# HT6872_D.net
KiCad netlist of a schematic drawn in EasyEDA Pro
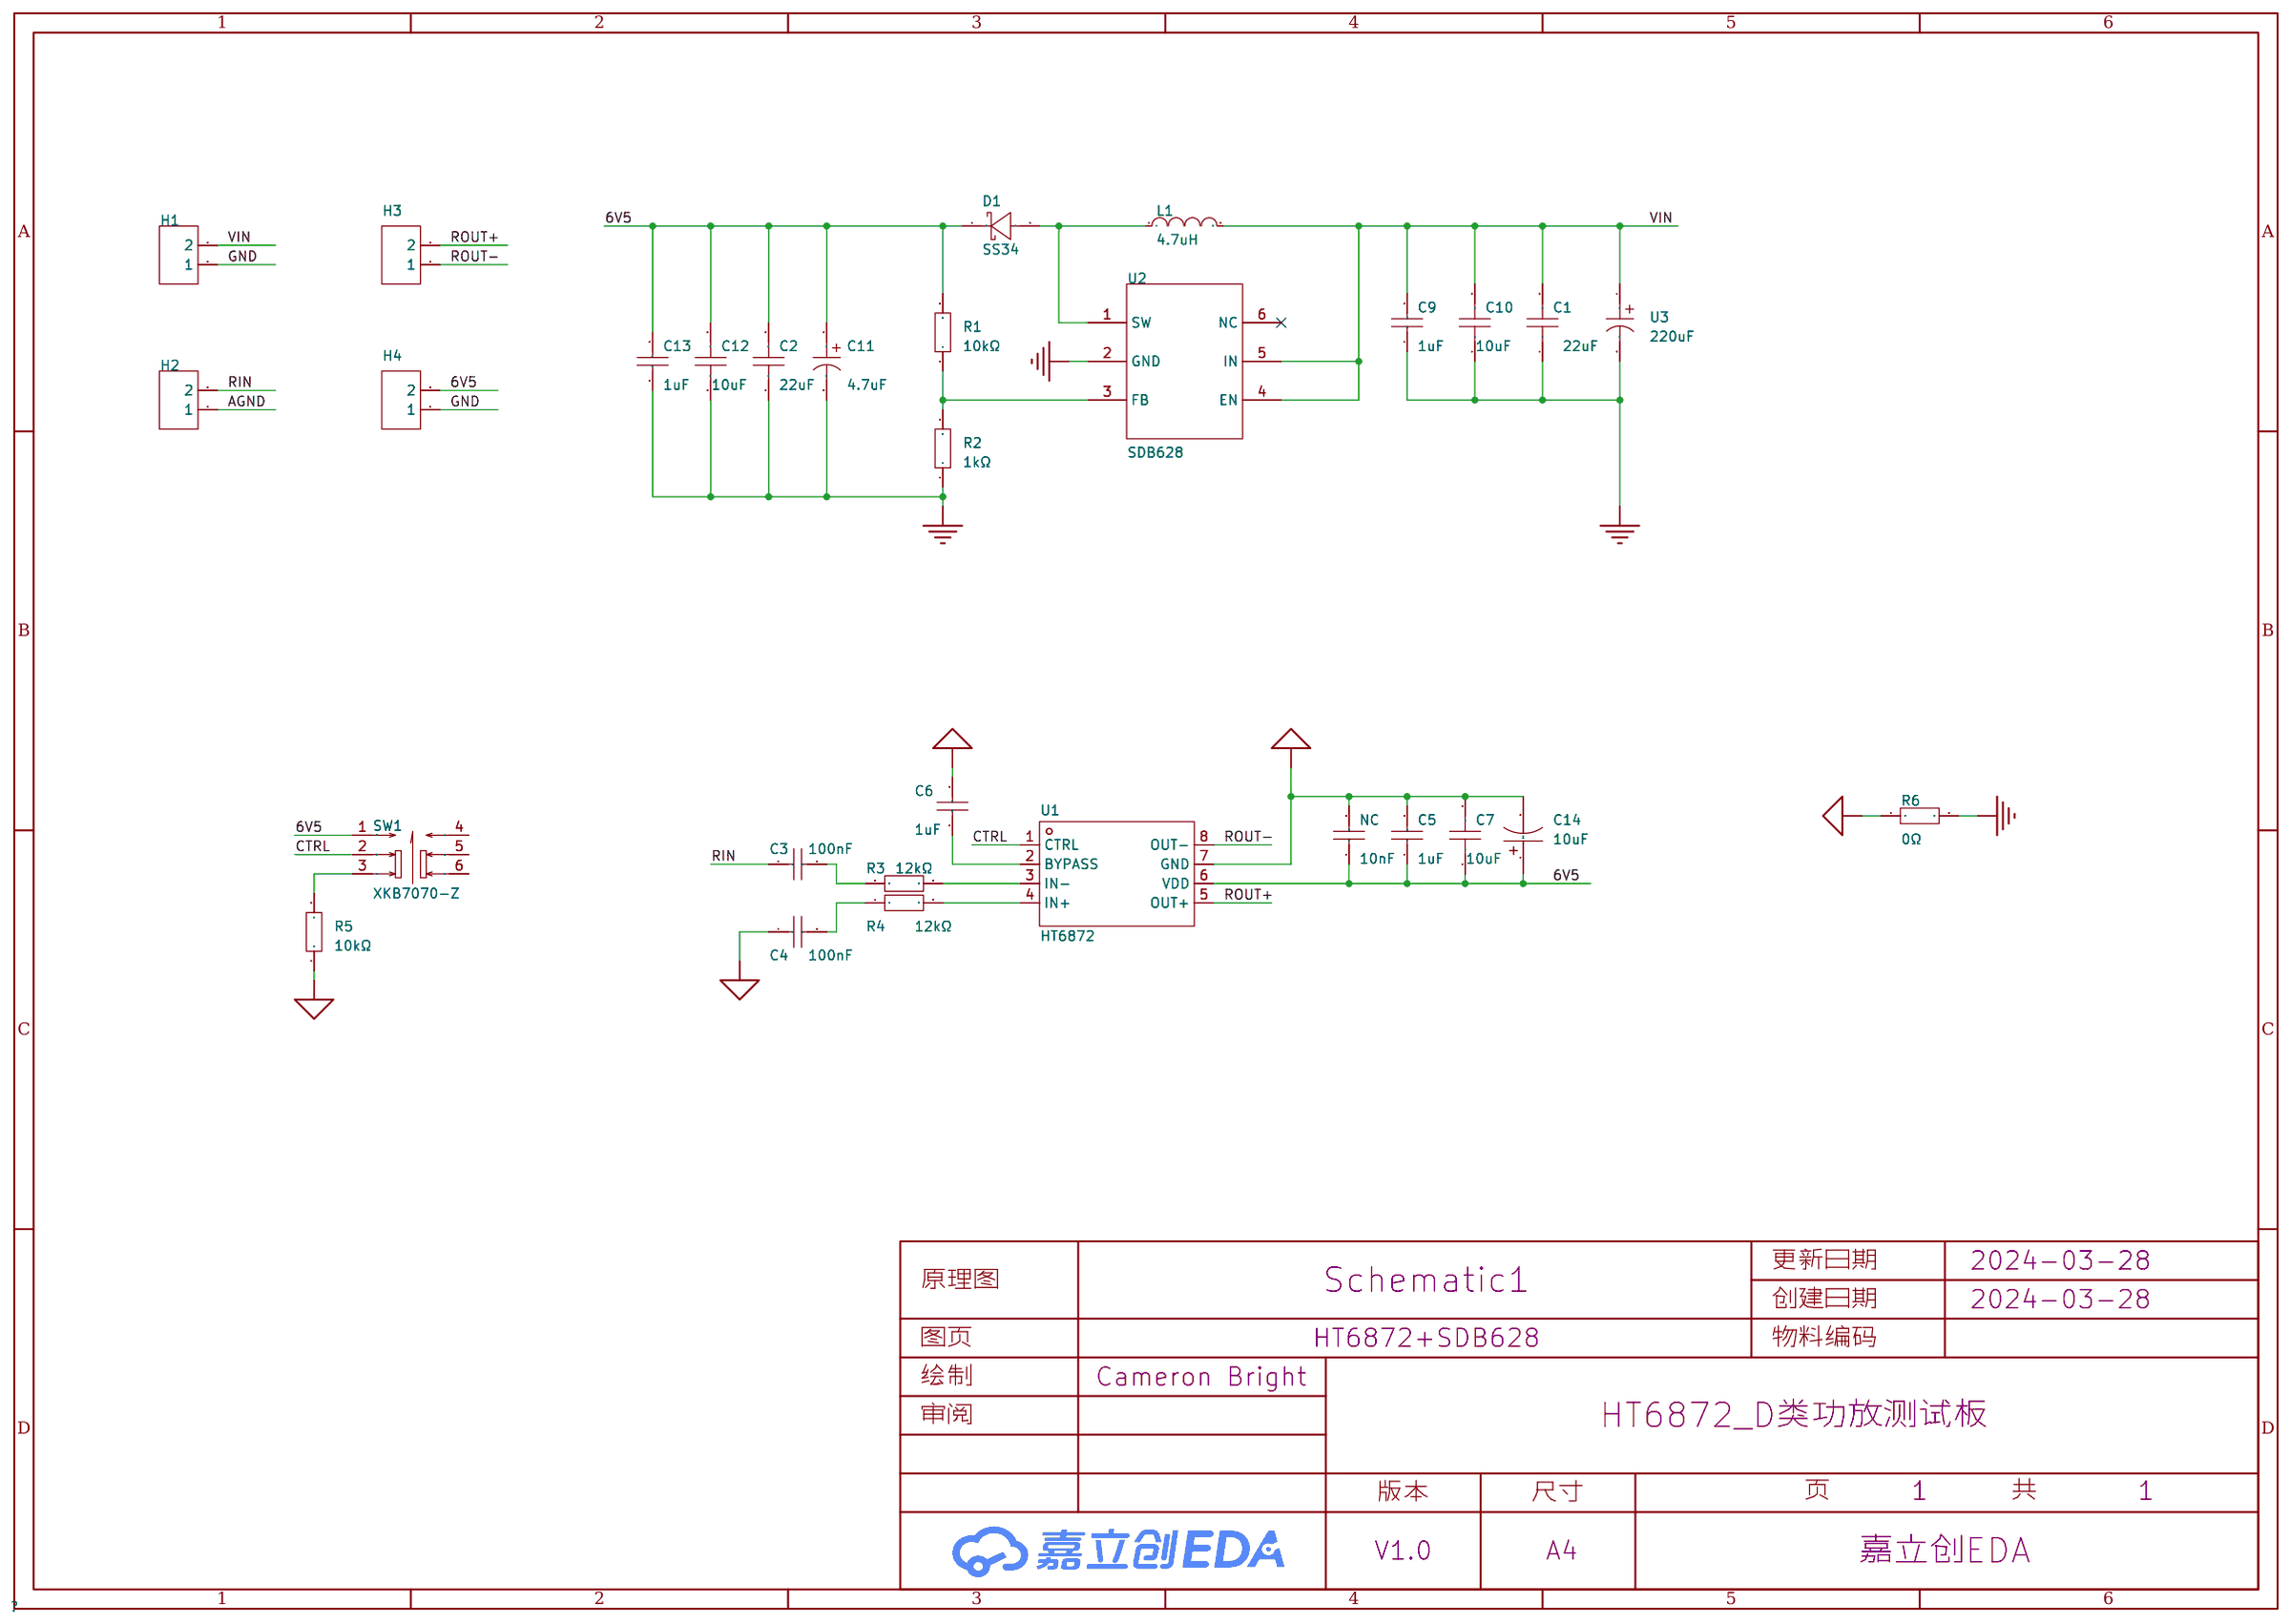
[diagram p0: schematic sheet]

(export (version "E")
  (design (tool "Eeschema 10.0.6"))
  (components
    (comp (ref "C1")
      (value "22uF")
      (footprint "easyedapro:C0603")
      (description "容值:22uF;精度:±20%;额定电压:6.3V;材质(温度系数):X5R;")
      (fields
        (field (name "Manufacturer Part") "CL10A226MQ8NRNC")
        (field (name "Manufacturer") "SAMSUNG(三星)")
      )
      (libsource (lib "easyedapro") (part "CL10A226MQ8NRNC"))
    )
    (comp (ref "C2")
      (value "22uF")
      (footprint "easyedapro:C0603")
      (description "容值:22uF;精度:±20%;额定电压:6.3V;材质(温度系数):X5R;")
      (fields
        (field (name "Manufacturer Part") "CL10A226MQ8NRNC")
        (field (name "Manufacturer") "SAMSUNG(三星)")
      )
      (libsource (lib "easyedapro") (part "CL10A226MQ8NRNC"))
    )
    (comp (ref "C3")
      (value "100nF")
      (footprint "easyedapro:C0603")
      (description "容值:100nF;精度:±10%;额定电压:50V;材质(温度系数):X7R;")
      (fields (field (name "Manufacturer Part") "0603B104K500NT") (field (name "Manufacturer") "FH(风华)"))
      (libsource (lib "easyedapro") (part "0603B104K500NT"))
    )
    (comp (ref "C4")
      (value "100nF")
      (footprint "easyedapro:C0603")
      (description "容值:100nF;精度:±10%;额定电压:50V;材质(温度系数):X7R;")
      (fields (field (name "Manufacturer Part") "0603B104K500NT") (field (name "Manufacturer") "FH(风华)"))
      (libsource (lib "easyedapro") (part "0603B104K500NT"))
    )
    (comp (ref "C5")
      (value "1uF")
      (footprint "easyedapro:C0603")
      (description "容值:1uF;精度:±10%;额定电压:50V;材质(温度系数):X5R;")
      (fields
        (field (name "Manufacturer Part") "CL10A105KB8NNNC")
        (field (name "Manufacturer") "SAMSUNG(三星)")
      )
      (libsource (lib "easyedapro") (part "CL10A105KB8NNNC"))
    )
    (comp (ref "C6")
      (value "1uF")
      (footprint "easyedapro:C0603")
      (description "容值:1uF;精度:±10%;额定电压:50V;材质(温度系数):X5R;")
      (fields
        (field (name "Manufacturer Part") "CL10A105KB8NNNC")
        (field (name "Manufacturer") "SAMSUNG(三星)")
      )
      (libsource (lib "easyedapro") (part "CL10A105KB8NNNC"))
    )
    (comp (ref "C7")
      (value "10uF")
      (footprint "easyedapro:C0603")
      (description "容值:10uF;精度:±10%;额定电压:10V;材质(温度系数):X5R;")
      (fields
        (field (name "Manufacturer Part") "CL10A106KP8NNNC")
        (field (name "Manufacturer") "SAMSUNG(三星)")
      )
      (libsource (lib "easyedapro") (part "CL10A106KP8NNNC"))
    )
    (comp (ref "C9")
      (value "1uF")
      (footprint "easyedapro:C0603")
      (description "容值:1uF;精度:±10%;额定电压:50V;材质(温度系数):X5R;")
      (fields
        (field (name "Manufacturer Part") "CL10A105KB8NNNC")
        (field (name "Manufacturer") "SAMSUNG(三星)")
      )
      (libsource (lib "easyedapro") (part "CL10A105KB8NNNC"))
    )
    (comp (ref "C10")
      (value "10uF")
      (footprint "easyedapro:C0603")
      (description "容值:10uF;精度:±10%;额定电压:10V;材质(温度系数):X5R;")
      (fields
        (field (name "Manufacturer Part") "CL10A106KP8NNNC")
        (field (name "Manufacturer") "SAMSUNG(三星)")
      )
      (libsource (lib "easyedapro") (part "CL10A106KP8NNNC"))
    )
    (comp (ref "C11")
      (value "4.7uF")
      (footprint "easyedapro:CAP-TH_BD5.0-P2.00-D0.5-FD")
      (description "容值:4.7uF;精度:±20%;额定电压:50V;纹波电流:-;等效串联电阻:-;")
      (fields (field (name "Manufacturer Part") "KM1H4R7M0407") (field (name "Manufacturer") "ROQANG(容强)"))
      (libsource (lib "easyedapro") (part "KM1H4R7M0407"))
    )
    (comp (ref "C12")
      (value "10uF")
      (footprint "easyedapro:C0603")
      (description "容值:10uF;精度:±10%;额定电压:10V;材质(温度系数):X5R;")
      (fields
        (field (name "Manufacturer Part") "CL10A106KP8NNNC")
        (field (name "Manufacturer") "SAMSUNG(三星)")
      )
      (libsource (lib "easyedapro") (part "CL10A106KP8NNNC"))
    )
    (comp (ref "C13")
      (value "1uF")
      (footprint "easyedapro:C0603")
      (description "容值:1uF;精度:±10%;额定电压:50V;材质(温度系数):X5R;")
      (fields
        (field (name "Manufacturer Part") "CL10A105KB8NNNC")
        (field (name "Manufacturer") "SAMSUNG(三星)")
      )
      (libsource (lib "easyedapro") (part "CL10A105KB8NNNC"))
    )
    (comp (ref "C14")
      (value "10uF")
      (footprint "easyedapro:CAP-TH_BD5.0-P2.00-D0.8-FD")
      (description "容值:10uF;精度:±20%;额定电压:50V;纹波电流:50mA@120Hz;等效串联电阻:-;")
      (fields
        (field (name "Manufacturer Part") "01EC1809SHC10UF50V")
        (field (name "Manufacturer") "KNSCHA(科尼盛)")
      )
      (libsource (lib "easyedapro") (part "01EC1809SHC10UF50V"))
    )
    (comp (ref "D1")
      (value "SS34")
      (footprint "easyedapro:SMA_L4.3-W2.5-LS5.0-RD")
      (description "二极管配置:独立式;正向压降(Vf):550mV@3A;直流反向耐压(Vr):40V;平均整流电流(Io):3A;")
      (fields (field (name "Manufacturer") "TWGMC(台湾迪嘉)"))
      (libsource (lib "easyedapro") (part "SS34_C727060"))
    )
    (comp (ref "H1")
      (value "~")
      (footprint "easyedapro:HDR-TH_2P-P2.54-V-F")
      (libsource (lib "easyedapro") (part "Header-Female-2.54_1x2"))
    )
    (comp (ref "H2")
      (value "~")
      (footprint "easyedapro:HDR-TH_2P-P2.54-V-F")
      (libsource (lib "easyedapro") (part "Header-Female-2.54_1x2"))
    )
    (comp (ref "H3")
      (value "~")
      (footprint "easyedapro:HDR-TH_2P-P2.54-V-F")
      (libsource (lib "easyedapro") (part "Header-Female-2.54_1x2"))
    )
    (comp (ref "H4")
      (value "~")
      (footprint "easyedapro:HDR-TH_2P-P2.54-V-F")
      (libsource (lib "easyedapro") (part "Header-Female-2.54_1x2"))
    )
    (comp (ref "L1")
      (value "4.7uH")
      (footprint "easyedapro:IND-SMD_L4.4-W4.2")
      (description "电感值:4.7uH;精度:±20%;额定电流:2.8A;饱和电流(Isat):3A;类型:一体成型电感;")
      (fields (field (name "Manufacturer Part") "FXL0420-4R7-M") (field (name "Manufacturer") "cjiang(长江微电)"))
      (libsource (lib "easyedapro") (part "FXL0420-4R7-M"))
    )
    (comp (ref "NC")
      (value "10nF")
      (footprint "easyedapro:C0603")
      (description "容值:10nF;精度:±10%;额定电压:50V;材质(温度系数):X7R;")
      (fields
        (field (name "Manufacturer Part") "CC0603KRX7R9BB103")
        (field (name "Manufacturer") "YAGEO(国巨)")
      )
      (libsource (lib "easyedapro") (part "CC0603KRX7R9BB103"))
    )
    (comp (ref "R1")
      (value "10kΩ")
      (footprint "easyedapro:R0603")
      (description "电阻类型:厚膜电阻;阻值:10kΩ;精度:±1%;功率:100mW;最大工作电压:75V;温度系数:±100ppm/°C;")
      (fields
        (field (name "Manufacturer Part") "0603WAF1002T5E")
        (field (name "Manufacturer") "UNI-ROYAL(厚声)")
      )
      (libsource (lib "easyedapro") (part "0603WAF1002T5E"))
    )
    (comp (ref "R2")
      (value "1kΩ")
      (footprint "easyedapro:R0603")
      (description "电阻类型:厚膜电阻;阻值:1kΩ;精度:±1%;功率:100mW;最大工作电压:75V;温度系数:±100ppm/°C;")
      (fields (field (name "Manufacturer Part") "RC0603FR-071KL") (field (name "Manufacturer") "YAGEO(国巨)"))
      (libsource (lib "easyedapro") (part "RC0603FR-071KL"))
    )
    (comp (ref "R3")
      (value "12kΩ")
      (footprint "easyedapro:R0603")
      (description "电阻类型:厚膜电阻;阻值:12kΩ;精度:±1%;功率:100mW;最大工作电压:75V;温度系数:±100ppm/°C;")
      (fields
        (field (name "Manufacturer Part") "0603WAF1202T5E")
        (field (name "Manufacturer") "UNI-ROYAL(厚声)")
      )
      (libsource (lib "easyedapro") (part "0603WAF1202T5E"))
    )
    (comp (ref "R4")
      (value "12kΩ")
      (footprint "easyedapro:R0603")
      (description "电阻类型:厚膜电阻;阻值:12kΩ;精度:±1%;功率:100mW;最大工作电压:75V;温度系数:±100ppm/°C;")
      (fields
        (field (name "Manufacturer Part") "0603WAF1202T5E")
        (field (name "Manufacturer") "UNI-ROYAL(厚声)")
      )
      (libsource (lib "easyedapro") (part "0603WAF1202T5E"))
    )
    (comp (ref "R5")
      (value "10kΩ")
      (footprint "easyedapro:R0603")
      (description "电阻类型:厚膜电阻;阻值:10kΩ;精度:±1%;功率:100mW;最大工作电压:75V;温度系数:±100ppm/°C;")
      (fields
        (field (name "Manufacturer Part") "0603WAF1002T5E")
        (field (name "Manufacturer") "UNI-ROYAL(厚声)")
      )
      (libsource (lib "easyedapro") (part "0603WAF1002T5E"))
    )
    (comp (ref "R6")
      (value "0Ω")
      (footprint "easyedapro:R0603")
      (description "电阻类型:厚膜电阻;阻值:0Ω;精度:±1%;功率:100mW;最大工作电压:75V;")
      (fields
        (field (name "Manufacturer Part") "0603WAF0000T5E")
        (field (name "Manufacturer") "UNI-ROYAL(厚声)")
      )
      (libsource (lib "easyedapro") (part "0603WAF0000T5E"))
    )
    (comp (ref "SW1")
      (value "XKB7070-Z")
      (footprint "easyedapro:SW-TH_6P-L7.0-W7.0-P2.00")
      (description "自锁/无锁:自锁;安装方式:直插;触点电流:100mA;额定电压 (AC):250V;额定电压 (DC):30V;带灯:不带;作用力:160gf;机械寿命:10万次;")
      (fields (field (name "Manufacturer") "XKB Connectivity(中国星坤)"))
      (libsource (lib "easyedapro") (part "XKB7070-Z"))
    )
    (comp (ref "U1")
      (value "HT6872")
      (footprint "easyedapro:SOP-8_L4.9-W3.9-P1.27-LS6.0-BL")
      (description "功放类型:D类功放;扬声器通道数:单声道;输出功率:3.85Wx1@4Ω;")
      (fields (field (name "Manufacturer") "嘉兴禾润"))
      (libsource (lib "easyedapro") (part "HT6872"))
    )
    (comp (ref "U2")
      (value "SDB628")
      (footprint "easyedapro:SOT-23-6_L2.9-W1.6-P0.95-LS2.8-BR")
      (description "功能类型:升压型;输入电压:2V~24V;输出电压:28V;输出电流(最大值):2A;")
      (fields (field (name "Manufacturer") "SHOUDING(首鼎半导体)"))
      (libsource (lib "easyedapro") (part "SDB628"))
    )
    (comp (ref "U3")
      (value "220uF")
      (footprint "easyedapro:CAP-TH_BD8.0-P3.50-D0.5-FD")
      (description "容值:220uF;精度:±20%;额定电压:35V;纹波电流:280mA@120kHz;等效串联电阻:-;")
      (fields (field (name "Manufacturer Part") "01EC1230") (field (name "Manufacturer") "KNSCHA(科尼盛)"))
      (libsource (lib "easyedapro") (part "01EC1230"))
    )
  )
  (nets
    (net (code "1") (name "/6V5") (class "Default")
      (node (ref "C11") (pin "1") (pinfunction "1_1") (pintype "input"))
      (node (ref "C12") (pin "2") (pinfunction "2_2") (pintype "unspecified"))
      (node (ref "C13") (pin "2") (pinfunction "2_2") (pintype "input"))
      (node (ref "C14") (pin "1") (pinfunction "1_1") (pintype "unspecified"))
      (node (ref "C2") (pin "2") (pinfunction "2_2") (pintype "unspecified"))
      (node (ref "C5") (pin "1") (pinfunction "1_1") (pintype "input"))
      (node (ref "C7") (pin "1") (pinfunction "1_1") (pintype "unspecified"))
      (node (ref "D1") (pin "1") (pinfunction "C_1") (pintype "unspecified"))
      (node (ref "H4") (pin "2") (pinfunction "2_2") (pintype "input"))
      (node (ref "NC") (pin "1") (pinfunction "1_1") (pintype "input"))
      (node (ref "R1") (pin "2") (pinfunction "2_2") (pintype "input"))
      (node (ref "SW1") (pin "1") (pinfunction "1_1") (pintype "unspecified"))
      (node (ref "U1") (pin "6") (pinfunction "VDD_6") (pintype "unspecified"))
    )
    (net (code "2") (name "/CTRL") (class "Default")
      (node (ref "SW1") (pin "2") (pinfunction "2_2") (pintype "unspecified"))
      (node (ref "U1") (pin "1") (pinfunction "CTRL_1") (pintype "unspecified"))
    )
    (net (code "3") (name "/RIN") (class "Default")
      (node (ref "C3") (pin "1") (pinfunction "1_1") (pintype "input"))
      (node (ref "H2") (pin "2") (pinfunction "2_2") (pintype "input"))
    )
    (net (code "4") (name "/ROUT+") (class "Default")
      (node (ref "H3") (pin "2") (pinfunction "2_2") (pintype "input"))
      (node (ref "U1") (pin "5") (pinfunction "OUT+_5") (pintype "unspecified"))
    )
    (net (code "5") (name "/ROUT-") (class "Default")
      (node (ref "H3") (pin "1") (pinfunction "1_1") (pintype "input"))
      (node (ref "U1") (pin "8") (pinfunction "OUT-_8") (pintype "unspecified"))
    )
    (net (code "6") (name "/VIN") (class "Default")
      (node (ref "C1") (pin "2") (pinfunction "2_2") (pintype "unspecified"))
      (node (ref "C10") (pin "2") (pinfunction "2_2") (pintype "unspecified"))
      (node (ref "C9") (pin "2") (pinfunction "2_2") (pintype "input"))
      (node (ref "H1") (pin "2") (pinfunction "2_2") (pintype "input"))
      (node (ref "L1") (pin "2") (pinfunction "2_2") (pintype "unspecified"))
      (node (ref "U2") (pin "4") (pinfunction "EN_4") (pintype "input"))
      (node (ref "U2") (pin "5") (pinfunction "IN_5") (pintype "input"))
      (node (ref "U3") (pin "1") (pinfunction "1_1") (pintype "input"))
    )
    (net (code "7") (name "AGND") (class "Default")
      (node (ref "C14") (pin "2") (pinfunction "2_2") (pintype "unspecified"))
      (node (ref "C4") (pin "1") (pinfunction "1_1") (pintype "input"))
      (node (ref "C5") (pin "2") (pinfunction "2_2") (pintype "input"))
      (node (ref "C6") (pin "2") (pinfunction "2_2") (pintype "input"))
      (node (ref "C7") (pin "2") (pinfunction "2_2") (pintype "unspecified"))
      (node (ref "H2") (pin "1") (pinfunction "1_1") (pintype "input"))
      (node (ref "NC") (pin "2") (pinfunction "2_2") (pintype "input"))
      (node (ref "R5") (pin "1") (pinfunction "1_1") (pintype "input"))
      (node (ref "R6") (pin "1") (pinfunction "1_1") (pintype "input"))
      (node (ref "U1") (pin "7") (pinfunction "GND_7") (pintype "unspecified"))
    )
    (net (code "8") (name "GND") (class "Default")
      (node (ref "C1") (pin "1") (pinfunction "1_1") (pintype "unspecified"))
      (node (ref "C10") (pin "1") (pinfunction "1_1") (pintype "unspecified"))
      (node (ref "C11") (pin "2") (pinfunction "2_2") (pintype "input"))
      (node (ref "C12") (pin "1") (pinfunction "1_1") (pintype "unspecified"))
      (node (ref "C13") (pin "1") (pinfunction "1_1") (pintype "input"))
      (node (ref "C2") (pin "1") (pinfunction "1_1") (pintype "unspecified"))
      (node (ref "C9") (pin "1") (pinfunction "1_1") (pintype "input"))
      (node (ref "H1") (pin "1") (pinfunction "1_1") (pintype "input"))
      (node (ref "H4") (pin "1") (pinfunction "1_1") (pintype "input"))
      (node (ref "R2") (pin "1") (pinfunction "1_1") (pintype "input"))
      (node (ref "R6") (pin "2") (pinfunction "2_2") (pintype "input"))
      (node (ref "U2") (pin "2") (pinfunction "GND_2") (pintype "input"))
      (node (ref "U3") (pin "2") (pinfunction "2_2") (pintype "input"))
    )
    (net (code "9") (name "Net-(C3-Pad2)") (class "Default")
      (node (ref "C3") (pin "2") (pinfunction "2_2") (pintype "input"))
      (node (ref "R3") (pin "1") (pinfunction "1_1") (pintype "input"))
    )
    (net (code "10") (name "Net-(C4-Pad2)") (class "Default")
      (node (ref "C4") (pin "2") (pinfunction "2_2") (pintype "input"))
      (node (ref "R4") (pin "1") (pinfunction "1_1") (pintype "input"))
    )
    (net (code "11") (name "Net-(D1-A)") (class "Default")
      (node (ref "D1") (pin "2") (pinfunction "A_2") (pintype "unspecified"))
      (node (ref "L1") (pin "1") (pinfunction "1_1") (pintype "unspecified"))
      (node (ref "U2") (pin "1") (pinfunction "SW_1") (pintype "input"))
    )
    (net (code "12") (name "Net-(R5-Pad2)") (class "Default")
      (node (ref "R5") (pin "2") (pinfunction "2_2") (pintype "input"))
      (node (ref "SW1") (pin "3") (pinfunction "3_3") (pintype "unspecified"))
    )
    (net (code "13") (name "Net-(U1-BYPASS)") (class "Default")
      (node (ref "C6") (pin "1") (pinfunction "1_1") (pintype "input"))
      (node (ref "U1") (pin "2") (pinfunction "BYPASS_2") (pintype "unspecified"))
    )
    (net (code "14") (name "Net-(U1-IN+)") (class "Default")
      (node (ref "R4") (pin "2") (pinfunction "2_2") (pintype "input"))
      (node (ref "U1") (pin "4") (pinfunction "IN+_4") (pintype "unspecified"))
    )
    (net (code "15") (name "Net-(U1-IN-)") (class "Default")
      (node (ref "R3") (pin "2") (pinfunction "2_2") (pintype "input"))
      (node (ref "U1") (pin "3") (pinfunction "IN-_3") (pintype "unspecified"))
    )
    (net (code "16") (name "Net-(U2-FB)") (class "Default")
      (node (ref "R1") (pin "1") (pinfunction "1_1") (pintype "input"))
      (node (ref "R2") (pin "2") (pinfunction "2_2") (pintype "input"))
      (node (ref "U2") (pin "3") (pinfunction "FB_3") (pintype "input"))
    )
    (net (code "17") (name "unconnected-(SW1-Pad4)") (class "Default")
      (node (ref "SW1") (pin "4") (pinfunction "4_4") (pintype "unspecified"))
    )
    (net (code "18") (name "unconnected-(SW1-Pad5)") (class "Default")
      (node (ref "SW1") (pin "5") (pinfunction "5_5") (pintype "unspecified"))
    )
    (net (code "19") (name "unconnected-(SW1-Pad6)") (class "Default")
      (node (ref "SW1") (pin "6") (pinfunction "6_6") (pintype "unspecified"))
    )
    (net (code "20") (name "unconnected-(U2-NC-Pad6)") (class "Default")
      (node (ref "U2") (pin "6") (pinfunction "NC_6") (pintype "input+no_connect"))
    )
  )
)
